# sd-adaptor-v_0_4.net
KiCad netlist of a schematic drawn in EAGLE
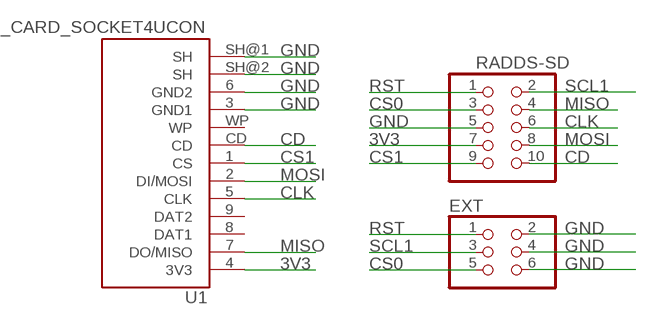
[diagram p0: schematic, sheet 1]

(export (version "E")
  (design (tool "Eeschema 10.0.6"))
  (components
    (comp (ref "EXT")
      (value "PINHD-2X3_2.54-SMD")
      (footprint "eagle-import:2X03SMD")
      (libsource (lib "eagle-import") (part "PINHD-2X3_2.54-SMD"))
    )
    (comp (ref "RADDS-SD")
      (value "PINHD-2X5_2.54-SMD")
      (footprint "eagle-import:2X05SMD")
      (libsource (lib "eagle-import") (part "PINHD-2X5_2.54-SMD"))
    )
    (comp (ref "U1")
      (value "SD_CARD_SOCKET4UCON")
      (footprint "eagle-import:SDCARD_4UCONN")
      (libsource (lib "eagle-import") (part "SD_CARD_SOCKET4UCON"))
    )
  )
  (nets
    (net (code "1") (name "/3V3") (class "Default")
      (node (ref "RADDS-SD") (pin "7") (pinfunction "7_7") (pintype "passive"))
      (node (ref "U1") (pin "4") (pinfunction "3V3_4") (pintype "power_in"))
    )
    (net (code "2") (name "/CD") (class "Default")
      (node (ref "RADDS-SD") (pin "10") (pinfunction "10_10") (pintype "passive"))
      (node (ref "U1") (pin "CD") (pinfunction "CD_CD") (pintype "bidirectional"))
    )
    (net (code "3") (name "/CLK") (class "Default")
      (node (ref "RADDS-SD") (pin "6") (pinfunction "6_6") (pintype "passive"))
      (node (ref "U1") (pin "5") (pinfunction "CLK_5") (pintype "bidirectional"))
    )
    (net (code "4") (name "/CS0") (class "Default")
      (node (ref "EXT") (pin "5") (pinfunction "5_5") (pintype "passive"))
      (node (ref "RADDS-SD") (pin "3") (pinfunction "3_3") (pintype "passive"))
    )
    (net (code "5") (name "/CS1") (class "Default")
      (node (ref "RADDS-SD") (pin "9") (pinfunction "9_9") (pintype "passive"))
      (node (ref "U1") (pin "1") (pinfunction "CS_1") (pintype "bidirectional"))
    )
    (net (code "6") (name "/GND") (class "Default")
      (node (ref "EXT") (pin "2") (pinfunction "2_2") (pintype "passive"))
      (node (ref "EXT") (pin "4") (pinfunction "4_4") (pintype "passive"))
      (node (ref "EXT") (pin "6") (pinfunction "6_6") (pintype "passive"))
      (node (ref "RADDS-SD") (pin "5") (pinfunction "5_5") (pintype "passive"))
      (node (ref "U1") (pin "3") (pinfunction "GND1_3") (pintype "power_in"))
      (node (ref "U1") (pin "6") (pinfunction "GND2_6") (pintype "power_in"))
      (node (ref "U1") (pin "SH@1") (pinfunction "SH_SH@1") (pintype "bidirectional"))
      (node (ref "U1") (pin "SH@2") (pinfunction "SH_SH@2") (pintype "bidirectional"))
    )
    (net (code "7") (name "/MISO") (class "Default")
      (node (ref "RADDS-SD") (pin "4") (pinfunction "4_4") (pintype "passive"))
      (node (ref "U1") (pin "7") (pinfunction "DO/MISO_7") (pintype "bidirectional"))
    )
    (net (code "8") (name "/MOSI") (class "Default")
      (node (ref "RADDS-SD") (pin "8") (pinfunction "8_8") (pintype "passive"))
      (node (ref "U1") (pin "2") (pinfunction "DI/MOSI_2") (pintype "bidirectional"))
    )
    (net (code "9") (name "/RST") (class "Default")
      (node (ref "EXT") (pin "1") (pinfunction "1_1") (pintype "passive"))
      (node (ref "RADDS-SD") (pin "1") (pinfunction "1_1") (pintype "passive"))
    )
    (net (code "10") (name "/SCL1") (class "Default")
      (node (ref "EXT") (pin "3") (pinfunction "3_3") (pintype "passive"))
      (node (ref "RADDS-SD") (pin "2") (pinfunction "2_2") (pintype "passive"))
    )
    (net (code "11") (name "unconnected-(U1-DAT1-Pad8)") (class "Default")
      (node (ref "U1") (pin "8") (pinfunction "DAT1_8") (pintype "bidirectional"))
    )
    (net (code "12") (name "unconnected-(U1-DAT2-Pad9)") (class "Default")
      (node (ref "U1") (pin "9") (pinfunction "DAT2_9") (pintype "bidirectional"))
    )
    (net (code "13") (name "unconnected-(U1-PadWP)") (class "Default")
      (node (ref "U1") (pin "WP") (pinfunction "WP_WP") (pintype "bidirectional"))
    )
  )
)
